# source_eagle.net
KiCad netlist of a schematic drawn in EAGLE
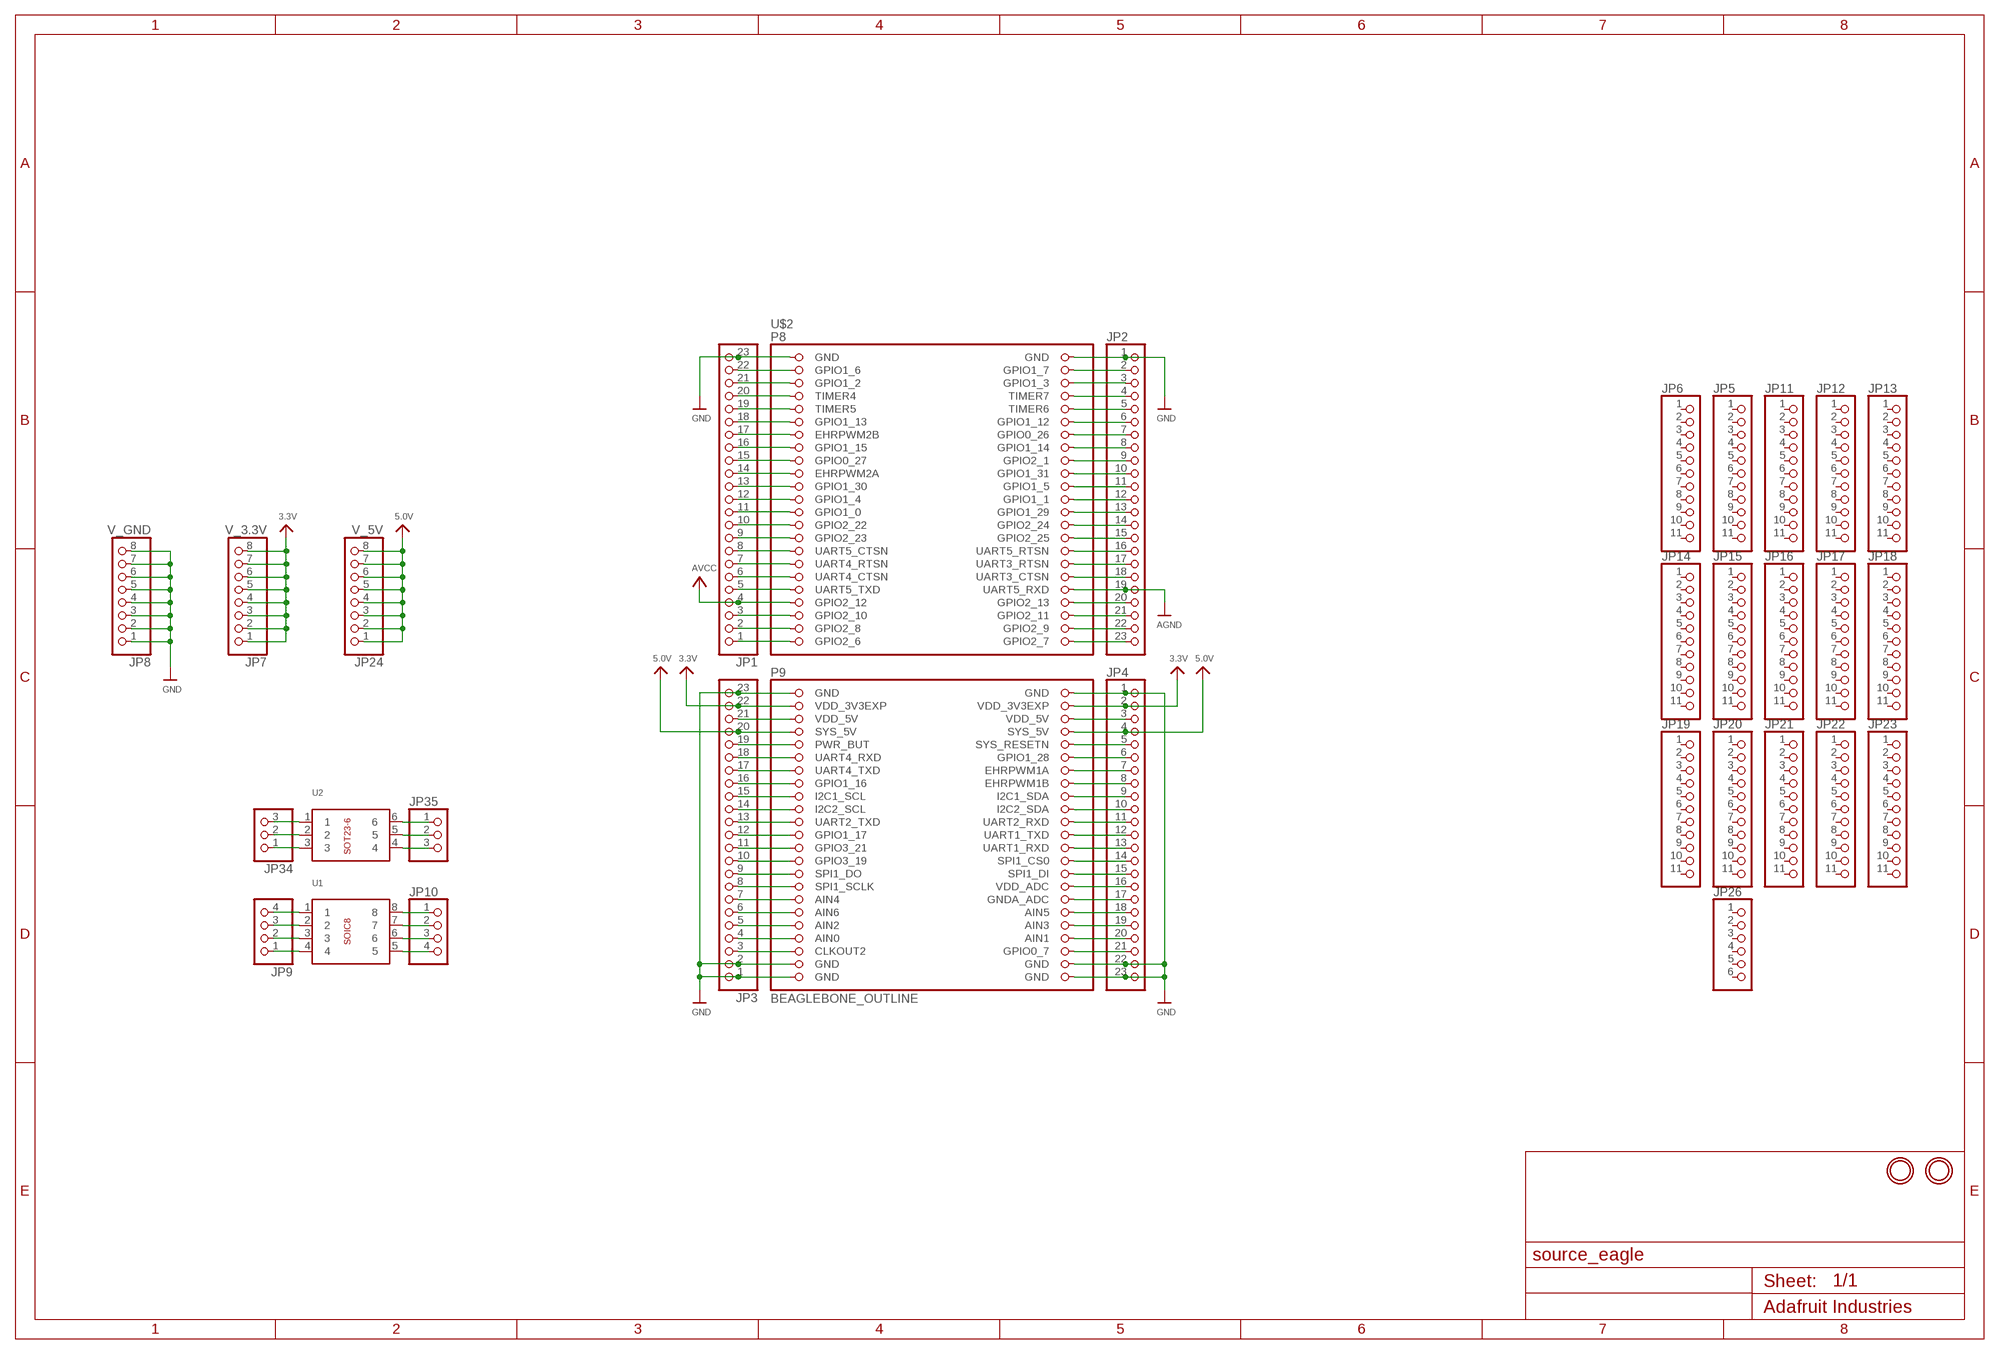
[diagram p0: schematic, sheet 1]

(export (version "E")
  (design (tool "Eeschema 10.0.6"))
  (components
    (comp (ref "JP1")
      (value "HEADER-1X23")
      (footprint "eagle-import:1X23_ROUND_70MIL")
      (libsource (lib "eagle-import") (part "HEADER-1X23"))
    )
    (comp (ref "JP2")
      (value "HEADER-1X23")
      (footprint "eagle-import:1X23_ROUND_70MIL")
      (libsource (lib "eagle-import") (part "HEADER-1X23"))
    )
    (comp (ref "JP3")
      (value "HEADER-1X23")
      (footprint "eagle-import:1X23_ROUND_70MIL")
      (libsource (lib "eagle-import") (part "HEADER-1X23"))
    )
    (comp (ref "JP4")
      (value "HEADER-1X23")
      (footprint "eagle-import:1X23_ROUND_70MIL")
      (libsource (lib "eagle-import") (part "HEADER-1X23"))
    )
    (comp (ref "JP5")
      (value "HEADER-1X1176MIL")
      (footprint "eagle-import:1X11_ROUND_76")
      (libsource (lib "eagle-import") (part "HEADER-1X1176MIL"))
    )
    (comp (ref "JP6")
      (value "HEADER-1X1176MIL")
      (footprint "eagle-import:1X11_ROUND_76")
      (libsource (lib "eagle-import") (part "HEADER-1X1176MIL"))
    )
    (comp (ref "JP7")
      (value "V_3.3V")
      (footprint "eagle-import:1X08_ROUND_70")
      (libsource (lib "eagle-import") (part "HEADER-1X870MIL"))
    )
    (comp (ref "JP8")
      (value "V_GND")
      (footprint "eagle-import:1X08_ROUND_70")
      (libsource (lib "eagle-import") (part "HEADER-1X870MIL"))
    )
    (comp (ref "JP9")
      (value "HEADER-1X476MIL")
      (footprint "eagle-import:1X04_ROUND_76")
      (libsource (lib "eagle-import") (part "HEADER-1X476MIL"))
    )
    (comp (ref "JP10")
      (value "HEADER-1X476MIL")
      (footprint "eagle-import:1X04_ROUND_76")
      (libsource (lib "eagle-import") (part "HEADER-1X476MIL"))
    )
    (comp (ref "JP11")
      (value "HEADER-1X1176MIL")
      (footprint "eagle-import:1X11_ROUND_76")
      (libsource (lib "eagle-import") (part "HEADER-1X1176MIL"))
    )
    (comp (ref "JP12")
      (value "HEADER-1X1176MIL")
      (footprint "eagle-import:1X11_ROUND_76")
      (libsource (lib "eagle-import") (part "HEADER-1X1176MIL"))
    )
    (comp (ref "JP13")
      (value "HEADER-1X1176MIL")
      (footprint "eagle-import:1X11_ROUND_76")
      (libsource (lib "eagle-import") (part "HEADER-1X1176MIL"))
    )
    (comp (ref "JP14")
      (value "HEADER-1X1176MIL")
      (footprint "eagle-import:1X11_ROUND_76")
      (libsource (lib "eagle-import") (part "HEADER-1X1176MIL"))
    )
    (comp (ref "JP15")
      (value "HEADER-1X1176MIL")
      (footprint "eagle-import:1X11_ROUND_76")
      (libsource (lib "eagle-import") (part "HEADER-1X1176MIL"))
    )
    (comp (ref "JP16")
      (value "HEADER-1X1176MIL")
      (footprint "eagle-import:1X11_ROUND_76")
      (libsource (lib "eagle-import") (part "HEADER-1X1176MIL"))
    )
    (comp (ref "JP17")
      (value "HEADER-1X1176MIL")
      (footprint "eagle-import:1X11_ROUND_76")
      (libsource (lib "eagle-import") (part "HEADER-1X1176MIL"))
    )
    (comp (ref "JP18")
      (value "HEADER-1X1176MIL")
      (footprint "eagle-import:1X11_ROUND_76")
      (libsource (lib "eagle-import") (part "HEADER-1X1176MIL"))
    )
    (comp (ref "JP19")
      (value "HEADER-1X1176MIL")
      (footprint "eagle-import:1X11_ROUND_76")
      (libsource (lib "eagle-import") (part "HEADER-1X1176MIL"))
    )
    (comp (ref "JP20")
      (value "HEADER-1X1176MIL")
      (footprint "eagle-import:1X11_ROUND_76")
      (libsource (lib "eagle-import") (part "HEADER-1X1176MIL"))
    )
    (comp (ref "JP21")
      (value "HEADER-1X1176MIL")
      (footprint "eagle-import:1X11_ROUND_76")
      (libsource (lib "eagle-import") (part "HEADER-1X1176MIL"))
    )
    (comp (ref "JP22")
      (value "HEADER-1X1176MIL")
      (footprint "eagle-import:1X11_ROUND_76")
      (libsource (lib "eagle-import") (part "HEADER-1X1176MIL"))
    )
    (comp (ref "JP23")
      (value "HEADER-1X1176MIL")
      (footprint "eagle-import:1X11_ROUND_76")
      (libsource (lib "eagle-import") (part "HEADER-1X1176MIL"))
    )
    (comp (ref "JP24")
      (value "V_5V")
      (footprint "eagle-import:1X08_ROUND_70")
      (libsource (lib "eagle-import") (part "HEADER-1X870MIL"))
    )
    (comp (ref "JP26")
      (value "HEADER-1X676MIL")
      (footprint "eagle-import:1X06_ROUND_76")
      (libsource (lib "eagle-import") (part "HEADER-1X676MIL"))
    )
    (comp (ref "JP34")
      (value "HEADER-1X376MIL")
      (footprint "eagle-import:1X03_ROUND_76")
      (libsource (lib "eagle-import") (part "HEADER-1X376MIL"))
    )
    (comp (ref "JP35")
      (value "HEADER-1X376MIL")
      (footprint "eagle-import:1X03_ROUND_76")
      (libsource (lib "eagle-import") (part "HEADER-1X376MIL"))
    )
    (comp (ref "U$2")
      (value "BEAGLEBONE_OUTLINE")
      (footprint "eagle-import:BEAGLEBONE_SHIELD")
      (libsource (lib "eagle-import") (part "BEAGLEBONE_OUTLINE"))
    )
    (comp (ref "U$22")
      (value "MOUNTINGHOLE3.0THIN")
      (footprint "eagle-import:MOUNTINGHOLE_3.0_PLATEDTHIN")
      (libsource (lib "eagle-import") (part "MOUNTINGHOLE3.0THIN"))
    )
    (comp (ref "U$23")
      (value "MOUNTINGHOLE3.0THIN")
      (footprint "eagle-import:MOUNTINGHOLE_3.0_PLATEDTHIN")
      (libsource (lib "eagle-import") (part "MOUNTINGHOLE3.0THIN"))
    )
    (comp (ref "U1")
      (value "BREAKOUT_SOIC8")
      (footprint "eagle-import:BREAKOUT_SOIC8")
      (libsource (lib "eagle-import") (part "BREAKOUT_SOIC8"))
    )
    (comp (ref "U2")
      (value "BREAKOUT_SOT23-6")
      (footprint "eagle-import:BREAKOUT_SOT23-6")
      (libsource (lib "eagle-import") (part "BREAKOUT_SOT23-6"))
    )
  )
  (nets
    (net (code "1") (name "3.3V") (class "Default")
      (node (ref "JP3") (pin "22") (pinfunction "22_22") (pintype "passive"))
      (node (ref "JP4") (pin "2") (pinfunction "2_2") (pintype "passive"))
      (node (ref "JP7") (pin "1") (pinfunction "1_1") (pintype "passive"))
      (node (ref "JP7") (pin "2") (pinfunction "2_2") (pintype "passive"))
      (node (ref "JP7") (pin "3") (pinfunction "3_3") (pintype "passive"))
      (node (ref "JP7") (pin "4") (pinfunction "4_4") (pintype "passive"))
      (node (ref "JP7") (pin "5") (pinfunction "5_5") (pintype "passive"))
      (node (ref "JP7") (pin "6") (pinfunction "6_6") (pintype "passive"))
      (node (ref "JP7") (pin "7") (pinfunction "7_7") (pintype "passive"))
      (node (ref "JP7") (pin "8") (pinfunction "8_8") (pintype "passive"))
      (node (ref "U$2") (pin "49") (pinfunction "VDD_3V3EXP_49") (pintype "power_in"))
      (node (ref "U$2") (pin "50") (pinfunction "VDD_3V3EXP_50") (pintype "power_in"))
    )
    (net (code "2") (name "5.0V") (class "Default")
      (node (ref "JP24") (pin "1") (pinfunction "1_1") (pintype "passive"))
      (node (ref "JP24") (pin "2") (pinfunction "2_2") (pintype "passive"))
      (node (ref "JP24") (pin "3") (pinfunction "3_3") (pintype "passive"))
      (node (ref "JP24") (pin "4") (pinfunction "4_4") (pintype "passive"))
      (node (ref "JP24") (pin "5") (pinfunction "5_5") (pintype "passive"))
      (node (ref "JP24") (pin "6") (pinfunction "6_6") (pintype "passive"))
      (node (ref "JP24") (pin "7") (pinfunction "7_7") (pintype "passive"))
      (node (ref "JP24") (pin "8") (pinfunction "8_8") (pintype "passive"))
      (node (ref "JP3") (pin "20") (pinfunction "20_20") (pintype "passive"))
      (node (ref "JP4") (pin "4") (pinfunction "4_4") (pintype "passive"))
      (node (ref "U$2") (pin "53") (pinfunction "SYS_5V_53") (pintype "passive"))
      (node (ref "U$2") (pin "54") (pinfunction "SYS_5V_54") (pintype "passive"))
    )
    (net (code "3") (name "AGND") (class "Default")
      (node (ref "JP2") (pin "19") (pinfunction "19_19") (pintype "passive"))
      (node (ref "U$2") (pin "38") (pinfunction "UART5_RXD_38") (pintype "passive"))
    )
    (net (code "4") (name "AVCC") (class "Default")
      (node (ref "JP1") (pin "4") (pinfunction "4_4") (pintype "passive"))
      (node (ref "U$2") (pin "39") (pinfunction "GPIO2_12_39") (pintype "passive"))
    )
    (net (code "5") (name "GND") (class "Default")
      (node (ref "JP1") (pin "23") (pinfunction "23_23") (pintype "passive"))
      (node (ref "JP2") (pin "1") (pinfunction "1_1") (pintype "passive"))
      (node (ref "JP3") (pin "1") (pinfunction "1_1") (pintype "passive"))
      (node (ref "JP3") (pin "2") (pinfunction "2_2") (pintype "passive"))
      (node (ref "JP3") (pin "23") (pinfunction "23_23") (pintype "passive"))
      (node (ref "JP4") (pin "1") (pinfunction "1_1") (pintype "passive"))
      (node (ref "JP4") (pin "22") (pinfunction "22_22") (pintype "passive"))
      (node (ref "JP4") (pin "23") (pinfunction "23_23") (pintype "passive"))
      (node (ref "JP8") (pin "1") (pinfunction "1_1") (pintype "passive"))
      (node (ref "JP8") (pin "2") (pinfunction "2_2") (pintype "passive"))
      (node (ref "JP8") (pin "3") (pinfunction "3_3") (pintype "passive"))
      (node (ref "JP8") (pin "4") (pinfunction "4_4") (pintype "passive"))
      (node (ref "JP8") (pin "5") (pinfunction "5_5") (pintype "passive"))
      (node (ref "JP8") (pin "6") (pinfunction "6_6") (pintype "passive"))
      (node (ref "JP8") (pin "7") (pinfunction "7_7") (pintype "passive"))
      (node (ref "JP8") (pin "8") (pinfunction "8_8") (pintype "passive"))
      (node (ref "U$2") (pin "1") (pinfunction "GND_1") (pintype "power_in"))
      (node (ref "U$2") (pin "2") (pinfunction "GND_2") (pintype "power_in"))
      (node (ref "U$2") (pin "47") (pinfunction "GND_47") (pintype "power_in"))
      (node (ref "U$2") (pin "48") (pinfunction "GND_48") (pintype "power_in"))
      (node (ref "U$2") (pin "89") (pinfunction "GND_89") (pintype "input"))
      (node (ref "U$2") (pin "90") (pinfunction "GND_90") (pintype "input"))
      (node (ref "U$2") (pin "91") (pinfunction "GND_91") (pintype "input"))
      (node (ref "U$2") (pin "92") (pinfunction "GND_92") (pintype "input"))
    )
    (net (code "6") (name "Net-(JP3-Pad21)") (class "Default")
      (node (ref "JP3") (pin "21") (pinfunction "21_21") (pintype "passive"))
      (node (ref "U$2") (pin "51") (pinfunction "VDD_5V_51") (pintype "power_in"))
    )
    (net (code "7") (name "Net-(JP4-Pad3)") (class "Default")
      (node (ref "JP4") (pin "3") (pinfunction "3_3") (pintype "passive"))
      (node (ref "U$2") (pin "52") (pinfunction "VDD_5V_52") (pintype "power_in"))
    )
    (net (code "8") (name "Net-(JP9-Pad1)") (class "Default")
      (node (ref "JP9") (pin "1") (pinfunction "1_1") (pintype "passive"))
      (node (ref "U1") (pin "4") (pinfunction "4_4") (pintype "bidirectional"))
    )
    (net (code "9") (name "Net-(JP9-Pad2)") (class "Default")
      (node (ref "JP9") (pin "2") (pinfunction "2_2") (pintype "passive"))
      (node (ref "U1") (pin "3") (pinfunction "3_3") (pintype "bidirectional"))
    )
    (net (code "10") (name "Net-(JP9-Pad3)") (class "Default")
      (node (ref "JP9") (pin "3") (pinfunction "3_3") (pintype "passive"))
      (node (ref "U1") (pin "2") (pinfunction "2_2") (pintype "bidirectional"))
    )
    (net (code "11") (name "Net-(JP9-Pad4)") (class "Default")
      (node (ref "JP9") (pin "4") (pinfunction "4_4") (pintype "passive"))
      (node (ref "U1") (pin "1") (pinfunction "1_1") (pintype "bidirectional"))
    )
    (net (code "12") (name "Net-(JP10-Pad1)") (class "Default")
      (node (ref "JP10") (pin "1") (pinfunction "1_1") (pintype "passive"))
      (node (ref "U1") (pin "8") (pinfunction "8_8") (pintype "bidirectional"))
    )
    (net (code "13") (name "Net-(JP10-Pad2)") (class "Default")
      (node (ref "JP10") (pin "2") (pinfunction "2_2") (pintype "passive"))
      (node (ref "U1") (pin "7") (pinfunction "7_7") (pintype "bidirectional"))
    )
    (net (code "14") (name "Net-(JP10-Pad3)") (class "Default")
      (node (ref "JP10") (pin "3") (pinfunction "3_3") (pintype "passive"))
      (node (ref "U1") (pin "6") (pinfunction "6_6") (pintype "bidirectional"))
    )
    (net (code "15") (name "Net-(JP10-Pad4)") (class "Default")
      (node (ref "JP10") (pin "4") (pinfunction "4_4") (pintype "passive"))
      (node (ref "U1") (pin "5") (pinfunction "5_5") (pintype "bidirectional"))
    )
    (net (code "16") (name "Net-(JP34-Pad1)") (class "Default")
      (node (ref "JP34") (pin "1") (pinfunction "1_1") (pintype "passive"))
      (node (ref "U2") (pin "3") (pinfunction "3_3") (pintype "bidirectional"))
    )
    (net (code "17") (name "Net-(JP34-Pad2)") (class "Default")
      (node (ref "JP34") (pin "2") (pinfunction "2_2") (pintype "passive"))
      (node (ref "U2") (pin "2") (pinfunction "2_2") (pintype "bidirectional"))
    )
    (net (code "18") (name "Net-(JP34-Pad3)") (class "Default")
      (node (ref "JP34") (pin "3") (pinfunction "3_3") (pintype "passive"))
      (node (ref "U2") (pin "1") (pinfunction "1_1") (pintype "bidirectional"))
    )
    (net (code "19") (name "Net-(JP35-Pad1)") (class "Default")
      (node (ref "JP35") (pin "1") (pinfunction "1_1") (pintype "passive"))
      (node (ref "U2") (pin "6") (pinfunction "6_6") (pintype "bidirectional"))
    )
    (net (code "20") (name "Net-(JP35-Pad2)") (class "Default")
      (node (ref "JP35") (pin "2") (pinfunction "2_2") (pintype "passive"))
      (node (ref "U2") (pin "5") (pinfunction "5_5") (pintype "bidirectional"))
    )
    (net (code "21") (name "Net-(JP35-Pad3)") (class "Default")
      (node (ref "JP35") (pin "3") (pinfunction "3_3") (pintype "passive"))
      (node (ref "U2") (pin "4") (pinfunction "4_4") (pintype "bidirectional"))
    )
    (net (code "22") (name "Net-(U$2-AIN0)") (class "Default")
      (node (ref "JP3") (pin "4") (pinfunction "4_4") (pintype "passive"))
      (node (ref "U$2") (pin "85") (pinfunction "AIN0_85") (pintype "power_in"))
    )
    (net (code "23") (name "Net-(U$2-AIN1)") (class "Default")
      (node (ref "JP4") (pin "20") (pinfunction "20_20") (pintype "passive"))
      (node (ref "U$2") (pin "86") (pinfunction "AIN1_86") (pintype "input"))
    )
    (net (code "24") (name "Net-(U$2-AIN2)") (class "Default")
      (node (ref "JP3") (pin "5") (pinfunction "5_5") (pintype "passive"))
      (node (ref "U$2") (pin "83") (pinfunction "AIN2_83") (pintype "passive"))
    )
    (net (code "25") (name "Net-(U$2-AIN3)") (class "Default")
      (node (ref "JP4") (pin "19") (pinfunction "19_19") (pintype "passive"))
      (node (ref "U$2") (pin "84") (pinfunction "AIN3_84") (pintype "power_in"))
    )
    (net (code "26") (name "Net-(U$2-AIN4)") (class "Default")
      (node (ref "JP3") (pin "7") (pinfunction "7_7") (pintype "passive"))
      (node (ref "U$2") (pin "79") (pinfunction "AIN4_79") (pintype "passive"))
    )
    (net (code "27") (name "Net-(U$2-AIN5)") (class "Default")
      (node (ref "JP4") (pin "18") (pinfunction "18_18") (pintype "passive"))
      (node (ref "U$2") (pin "82") (pinfunction "AIN5_82") (pintype "passive"))
    )
    (net (code "28") (name "Net-(U$2-AIN6)") (class "Default")
      (node (ref "JP3") (pin "6") (pinfunction "6_6") (pintype "passive"))
      (node (ref "U$2") (pin "81") (pinfunction "AIN6_81") (pintype "passive"))
    )
    (net (code "29") (name "Net-(U$2-CLKOUT2)") (class "Default")
      (node (ref "JP3") (pin "3") (pinfunction "3_3") (pintype "passive"))
      (node (ref "U$2") (pin "87") (pinfunction "CLKOUT2_87") (pintype "input"))
    )
    (net (code "30") (name "Net-(U$2-EHRPWM1A)") (class "Default")
      (node (ref "JP4") (pin "7") (pinfunction "7_7") (pintype "passive"))
      (node (ref "U$2") (pin "60") (pinfunction "EHRPWM1A_60") (pintype "passive"))
    )
    (net (code "31") (name "Net-(U$2-EHRPWM1B)") (class "Default")
      (node (ref "JP4") (pin "8") (pinfunction "8_8") (pintype "passive"))
      (node (ref "U$2") (pin "62") (pinfunction "EHRPWM1B_62") (pintype "passive"))
    )
    (net (code "32") (name "Net-(U$2-EHRPWM2A)") (class "Default")
      (node (ref "JP1") (pin "14") (pinfunction "14_14") (pintype "passive"))
      (node (ref "U$2") (pin "19") (pinfunction "EHRPWM2A_19") (pintype "passive"))
    )
    (net (code "33") (name "Net-(U$2-EHRPWM2B)") (class "Default")
      (node (ref "JP1") (pin "17") (pinfunction "17_17") (pintype "passive"))
      (node (ref "U$2") (pin "13") (pinfunction "EHRPWM2B_13") (pintype "passive"))
    )
    (net (code "34") (name "Net-(U$2-GNDA_ADC)") (class "Default")
      (node (ref "JP4") (pin "17") (pinfunction "17_17") (pintype "passive"))
      (node (ref "U$2") (pin "80") (pinfunction "GNDA_ADC_80") (pintype "passive"))
    )
    (net (code "35") (name "Net-(U$2-GPIO0_7)") (class "Default")
      (node (ref "JP4") (pin "21") (pinfunction "21_21") (pintype "passive"))
      (node (ref "U$2") (pin "88") (pinfunction "GPIO0_7_88") (pintype "input"))
    )
    (net (code "36") (name "Net-(U$2-GPIO0_26)") (class "Default")
      (node (ref "JP2") (pin "7") (pinfunction "7_7") (pintype "passive"))
      (node (ref "U$2") (pin "14") (pinfunction "GPIO0_26_14") (pintype "passive"))
    )
    (net (code "37") (name "Net-(U$2-GPIO0_27)") (class "Default")
      (node (ref "JP1") (pin "15") (pinfunction "15_15") (pintype "passive"))
      (node (ref "U$2") (pin "17") (pinfunction "GPIO0_27_17") (pintype "passive"))
    )
    (net (code "38") (name "Net-(U$2-GPIO1_0)") (class "Default")
      (node (ref "JP1") (pin "11") (pinfunction "11_11") (pintype "passive"))
      (node (ref "U$2") (pin "25") (pinfunction "GPIO1_0_25") (pintype "passive"))
    )
    (net (code "39") (name "Net-(U$2-GPIO1_1)") (class "Default")
      (node (ref "JP2") (pin "12") (pinfunction "12_12") (pintype "passive"))
      (node (ref "U$2") (pin "24") (pinfunction "GPIO1_1_24") (pintype "passive"))
    )
    (net (code "40") (name "Net-(U$2-GPIO1_2)") (class "Default")
      (node (ref "JP1") (pin "21") (pinfunction "21_21") (pintype "passive"))
      (node (ref "U$2") (pin "5") (pinfunction "GPIO1_2_5") (pintype "passive"))
    )
    (net (code "41") (name "Net-(U$2-GPIO1_3)") (class "Default")
      (node (ref "JP2") (pin "3") (pinfunction "3_3") (pintype "passive"))
      (node (ref "U$2") (pin "6") (pinfunction "GPIO1_3_6") (pintype "passive"))
    )
    (net (code "42") (name "Net-(U$2-GPIO1_4)") (class "Default")
      (node (ref "JP1") (pin "12") (pinfunction "12_12") (pintype "passive"))
      (node (ref "U$2") (pin "23") (pinfunction "GPIO1_4_23") (pintype "passive"))
    )
    (net (code "43") (name "Net-(U$2-GPIO1_5)") (class "Default")
      (node (ref "JP2") (pin "11") (pinfunction "11_11") (pintype "passive"))
      (node (ref "U$2") (pin "22") (pinfunction "GPIO1_5_22") (pintype "passive"))
    )
    (net (code "44") (name "Net-(U$2-GPIO1_6)") (class "Default")
      (node (ref "JP1") (pin "22") (pinfunction "22_22") (pintype "passive"))
      (node (ref "U$2") (pin "3") (pinfunction "GPIO1_6_3") (pintype "power_in"))
    )
    (net (code "45") (name "Net-(U$2-GPIO1_7)") (class "Default")
      (node (ref "JP2") (pin "2") (pinfunction "2_2") (pintype "passive"))
      (node (ref "U$2") (pin "4") (pinfunction "GPIO1_7_4") (pintype "power_in"))
    )
    (net (code "46") (name "Net-(U$2-GPIO1_12)") (class "Default")
      (node (ref "JP2") (pin "6") (pinfunction "6_6") (pintype "passive"))
      (node (ref "U$2") (pin "12") (pinfunction "GPIO1_12_12") (pintype "passive"))
    )
    (net (code "47") (name "Net-(U$2-GPIO1_13)") (class "Default")
      (node (ref "JP1") (pin "18") (pinfunction "18_18") (pintype "passive"))
      (node (ref "U$2") (pin "11") (pinfunction "GPIO1_13_11") (pintype "passive"))
    )
    (net (code "48") (name "Net-(U$2-GPIO1_14)") (class "Default")
      (node (ref "JP2") (pin "8") (pinfunction "8_8") (pintype "passive"))
      (node (ref "U$2") (pin "16") (pinfunction "GPIO1_14_16") (pintype "passive"))
    )
    (net (code "49") (name "Net-(U$2-GPIO1_15)") (class "Default")
      (node (ref "JP1") (pin "16") (pinfunction "16_16") (pintype "passive"))
      (node (ref "U$2") (pin "15") (pinfunction "GPIO1_15_15") (pintype "passive"))
    )
    (net (code "50") (name "Net-(U$2-GPIO1_16)") (class "Default")
      (node (ref "JP3") (pin "16") (pinfunction "16_16") (pintype "passive"))
      (node (ref "U$2") (pin "61") (pinfunction "GPIO1_16_61") (pintype "passive"))
    )
    (net (code "51") (name "Net-(U$2-GPIO1_17)") (class "Default")
      (node (ref "JP3") (pin "12") (pinfunction "12_12") (pintype "passive"))
      (node (ref "U$2") (pin "69") (pinfunction "GPIO1_17_69") (pintype "passive"))
    )
    (net (code "52") (name "Net-(U$2-GPIO1_28)") (class "Default")
      (node (ref "JP4") (pin "6") (pinfunction "6_6") (pintype "passive"))
      (node (ref "U$2") (pin "58") (pinfunction "GPIO1_28_58") (pintype "passive"))
    )
    (net (code "53") (name "Net-(U$2-GPIO1_29)") (class "Default")
      (node (ref "JP2") (pin "13") (pinfunction "13_13") (pintype "passive"))
      (node (ref "U$2") (pin "26") (pinfunction "GPIO1_29_26") (pintype "passive"))
    )
    (net (code "54") (name "Net-(U$2-GPIO1_30)") (class "Default")
      (node (ref "JP1") (pin "13") (pinfunction "13_13") (pintype "passive"))
      (node (ref "U$2") (pin "21") (pinfunction "GPIO1_30_21") (pintype "passive"))
    )
    (net (code "55") (name "Net-(U$2-GPIO1_31)") (class "Default")
      (node (ref "JP2") (pin "10") (pinfunction "10_10") (pintype "passive"))
      (node (ref "U$2") (pin "20") (pinfunction "GPIO1_31_20") (pintype "passive"))
    )
    (net (code "56") (name "Net-(U$2-GPIO2_1)") (class "Default")
      (node (ref "JP2") (pin "9") (pinfunction "9_9") (pintype "passive"))
      (node (ref "U$2") (pin "18") (pinfunction "GPIO2_1_18") (pintype "passive"))
    )
    (net (code "57") (name "Net-(U$2-GPIO2_6)") (class "Default")
      (node (ref "JP1") (pin "1") (pinfunction "1_1") (pintype "passive"))
      (node (ref "U$2") (pin "45") (pinfunction "GPIO2_6_45") (pintype "power_in"))
    )
    (net (code "58") (name "Net-(U$2-GPIO2_7)") (class "Default")
      (node (ref "JP2") (pin "23") (pinfunction "23_23") (pintype "passive"))
      (node (ref "U$2") (pin "46") (pinfunction "GPIO2_7_46") (pintype "power_in"))
    )
    (net (code "59") (name "Net-(U$2-GPIO2_8)") (class "Default")
      (node (ref "JP1") (pin "2") (pinfunction "2_2") (pintype "passive"))
      (node (ref "U$2") (pin "43") (pinfunction "GPIO2_8_43") (pintype "power_in"))
    )
    (net (code "60") (name "Net-(U$2-GPIO2_9)") (class "Default")
      (node (ref "JP2") (pin "22") (pinfunction "22_22") (pintype "passive"))
      (node (ref "U$2") (pin "44") (pinfunction "GPIO2_9_44") (pintype "power_in"))
    )
    (net (code "61") (name "Net-(U$2-GPIO2_10)") (class "Default")
      (node (ref "JP1") (pin "3") (pinfunction "3_3") (pintype "passive"))
      (node (ref "U$2") (pin "41") (pinfunction "GPIO2_10_41") (pintype "passive"))
    )
    (net (code "62") (name "Net-(U$2-GPIO2_11)") (class "Default")
      (node (ref "JP2") (pin "21") (pinfunction "21_21") (pintype "passive"))
      (node (ref "U$2") (pin "42") (pinfunction "GPIO2_11_42") (pintype "power_in"))
    )
    (net (code "63") (name "Net-(U$2-GPIO2_13)") (class "Default")
      (node (ref "JP2") (pin "20") (pinfunction "20_20") (pintype "passive"))
      (node (ref "U$2") (pin "40") (pinfunction "GPIO2_13_40") (pintype "passive"))
    )
    (net (code "64") (name "Net-(U$2-GPIO2_22)") (class "Default")
      (node (ref "JP1") (pin "10") (pinfunction "10_10") (pintype "passive"))
      (node (ref "U$2") (pin "27") (pinfunction "GPIO2_22_27") (pintype "passive"))
    )
    (net (code "65") (name "Net-(U$2-GPIO2_23)") (class "Default")
      (node (ref "JP1") (pin "9") (pinfunction "9_9") (pintype "passive"))
      (node (ref "U$2") (pin "29") (pinfunction "GPIO2_23_29") (pintype "passive"))
    )
    (net (code "66") (name "Net-(U$2-GPIO2_24)") (class "Default")
      (node (ref "JP2") (pin "14") (pinfunction "14_14") (pintype "passive"))
      (node (ref "U$2") (pin "28") (pinfunction "GPIO2_24_28") (pintype "passive"))
    )
    (net (code "67") (name "Net-(U$2-GPIO2_25)") (class "Default")
      (node (ref "JP2") (pin "15") (pinfunction "15_15") (pintype "passive"))
      (node (ref "U$2") (pin "30") (pinfunction "GPIO2_25_30") (pintype "passive"))
    )
    (net (code "68") (name "Net-(U$2-GPIO3_19)") (class "Default")
      (node (ref "JP3") (pin "10") (pinfunction "10_10") (pintype "passive"))
      (node (ref "U$2") (pin "73") (pinfunction "GPIO3_19_73") (pintype "passive"))
    )
    (net (code "69") (name "Net-(U$2-GPIO3_21)") (class "Default")
      (node (ref "JP3") (pin "11") (pinfunction "11_11") (pintype "passive"))
      (node (ref "U$2") (pin "71") (pinfunction "GPIO3_21_71") (pintype "passive"))
    )
    (net (code "70") (name "Net-(U$2-I2C1_SCL)") (class "Default")
      (node (ref "JP3") (pin "15") (pinfunction "15_15") (pintype "passive"))
      (node (ref "U$2") (pin "63") (pinfunction "I2C1_SCL_63") (pintype "passive"))
    )
    (net (code "71") (name "Net-(U$2-I2C1_SDA)") (class "Default")
      (node (ref "JP4") (pin "9") (pinfunction "9_9") (pintype "passive"))
      (node (ref "U$2") (pin "64") (pinfunction "I2C1_SDA_64") (pintype "passive"))
    )
    (net (code "72") (name "Net-(U$2-I2C2_SCL)") (class "Default")
      (node (ref "JP3") (pin "14") (pinfunction "14_14") (pintype "passive"))
      (node (ref "U$2") (pin "65") (pinfunction "I2C2_SCL_65") (pintype "passive"))
    )
    (net (code "73") (name "Net-(U$2-I2C2_SDA)") (class "Default")
      (node (ref "JP4") (pin "10") (pinfunction "10_10") (pintype "passive"))
      (node (ref "U$2") (pin "66") (pinfunction "I2C2_SDA_66") (pintype "passive"))
    )
    (net (code "74") (name "Net-(U$2-PWR_BUT)") (class "Default")
      (node (ref "JP3") (pin "19") (pinfunction "19_19") (pintype "passive"))
      (node (ref "U$2") (pin "55") (pinfunction "PWR_BUT_55") (pintype "passive"))
    )
    (net (code "75") (name "Net-(U$2-SPI1_CS0)") (class "Default")
      (node (ref "JP4") (pin "14") (pinfunction "14_14") (pintype "passive"))
      (node (ref "U$2") (pin "74") (pinfunction "SPI1_CS0_74") (pintype "passive"))
    )
    (net (code "76") (name "Net-(U$2-SPI1_DI)") (class "Default")
      (node (ref "JP4") (pin "15") (pinfunction "15_15") (pintype "passive"))
      (node (ref "U$2") (pin "76") (pinfunction "SPI1_DI_76") (pintype "passive"))
    )
    (net (code "77") (name "Net-(U$2-SPI1_DO)") (class "Default")
      (node (ref "JP3") (pin "9") (pinfunction "9_9") (pintype "passive"))
      (node (ref "U$2") (pin "75") (pinfunction "SPI1_DO_75") (pintype "passive"))
    )
    (net (code "78") (name "Net-(U$2-SPI1_SCLK)") (class "Default")
      (node (ref "JP3") (pin "8") (pinfunction "8_8") (pintype "passive"))
      (node (ref "U$2") (pin "77") (pinfunction "SPI1_SCLK_77") (pintype "passive"))
    )
    (net (code "79") (name "Net-(U$2-SYS_RESETN)") (class "Default")
      (node (ref "JP4") (pin "5") (pinfunction "5_5") (pintype "passive"))
      (node (ref "U$2") (pin "56") (pinfunction "SYS_RESETN_56") (pintype "passive"))
    )
    (net (code "80") (name "Net-(U$2-TIMER4)") (class "Default")
      (node (ref "JP1") (pin "20") (pinfunction "20_20") (pintype "passive"))
      (node (ref "U$2") (pin "7") (pinfunction "TIMER4_7") (pintype "passive"))
    )
    (net (code "81") (name "Net-(U$2-TIMER5)") (class "Default")
      (node (ref "JP1") (pin "19") (pinfunction "19_19") (pintype "passive"))
      (node (ref "U$2") (pin "9") (pinfunction "TIMER5_9") (pintype "passive"))
    )
    (net (code "82") (name "Net-(U$2-TIMER6)") (class "Default")
      (node (ref "JP2") (pin "5") (pinfunction "5_5") (pintype "passive"))
      (node (ref "U$2") (pin "10") (pinfunction "TIMER6_10") (pintype "passive"))
    )
    (net (code "83") (name "Net-(U$2-TIMER7)") (class "Default")
      (node (ref "JP2") (pin "4") (pinfunction "4_4") (pintype "passive"))
      (node (ref "U$2") (pin "8") (pinfunction "TIMER7_8") (pintype "passive"))
    )
    (net (code "84") (name "Net-(U$2-UART1_RXD)") (class "Default")
      (node (ref "JP4") (pin "13") (pinfunction "13_13") (pintype "passive"))
      (node (ref "U$2") (pin "72") (pinfunction "UART1_RXD_72") (pintype "passive"))
    )
    (net (code "85") (name "Net-(U$2-UART1_TXD)") (class "Default")
      (node (ref "JP4") (pin "12") (pinfunction "12_12") (pintype "passive"))
      (node (ref "U$2") (pin "70") (pinfunction "UART1_TXD_70") (pintype "passive"))
    )
    (net (code "86") (name "Net-(U$2-UART2_RXD)") (class "Default")
      (node (ref "JP4") (pin "11") (pinfunction "11_11") (pintype "passive"))
      (node (ref "U$2") (pin "68") (pinfunction "UART2_RXD_68") (pintype "passive"))
    )
    (net (code "87") (name "Net-(U$2-UART2_TXD)") (class "Default")
      (node (ref "JP3") (pin "13") (pinfunction "13_13") (pintype "passive"))
      (node (ref "U$2") (pin "67") (pinfunction "UART2_TXD_67") (pintype "passive"))
    )
    (net (code "88") (name "Net-(U$2-UART3_CTSN)") (class "Default")
      (node (ref "JP2") (pin "18") (pinfunction "18_18") (pintype "passive"))
      (node (ref "U$2") (pin "36") (pinfunction "UART3_CTSN_36") (pintype "passive"))
    )
    (net (code "89") (name "Net-(U$2-UART3_RTSN)") (class "Default")
      (node (ref "JP2") (pin "17") (pinfunction "17_17") (pintype "passive"))
      (node (ref "U$2") (pin "34") (pinfunction "UART3_RTSN_34") (pintype "passive"))
    )
    (net (code "90") (name "Net-(U$2-UART4_CTSN)") (class "Default")
      (node (ref "JP1") (pin "6") (pinfunction "6_6") (pintype "passive"))
      (node (ref "U$2") (pin "35") (pinfunction "UART4_CTSN_35") (pintype "passive"))
    )
    (net (code "91") (name "Net-(U$2-UART4_RTSN)") (class "Default")
      (node (ref "JP1") (pin "7") (pinfunction "7_7") (pintype "passive"))
      (node (ref "U$2") (pin "33") (pinfunction "UART4_RTSN_33") (pintype "passive"))
    )
    (net (code "92") (name "Net-(U$2-UART4_RXD)") (class "Default")
      (node (ref "JP3") (pin "18") (pinfunction "18_18") (pintype "passive"))
      (node (ref "U$2") (pin "57") (pinfunction "UART4_RXD_57") (pintype "passive"))
    )
    (net (code "93") (name "Net-(U$2-UART4_TXD)") (class "Default")
      (node (ref "JP3") (pin "17") (pinfunction "17_17") (pintype "passive"))
      (node (ref "U$2") (pin "59") (pinfunction "UART4_TXD_59") (pintype "passive"))
    )
    (net (code "94") (name "Net-(U$2-UART5_CTSN)") (class "Default")
      (node (ref "JP1") (pin "8") (pinfunction "8_8") (pintype "passive"))
      (node (ref "U$2") (pin "31") (pinfunction "UART5_CTSN_31") (pintype "passive"))
    )
    (net (code "95") (name "Net-(U$2-UART5_RTSN)") (class "Default")
      (node (ref "JP2") (pin "16") (pinfunction "16_16") (pintype "passive"))
      (node (ref "U$2") (pin "32") (pinfunction "UART5_RTSN_32") (pintype "passive"))
    )
    (net (code "96") (name "Net-(U$2-UART5_TXD)") (class "Default")
      (node (ref "JP1") (pin "5") (pinfunction "5_5") (pintype "passive"))
      (node (ref "U$2") (pin "37") (pinfunction "UART5_TXD_37") (pintype "passive"))
    )
    (net (code "97") (name "Net-(U$2-VDD_ADC)") (class "Default")
      (node (ref "JP4") (pin "16") (pinfunction "16_16") (pintype "passive"))
      (node (ref "U$2") (pin "78") (pinfunction "VDD_ADC_78") (pintype "passive"))
    )
    (net (code "98") (name "unconnected-(JP5-Pad1)") (class "Default")
      (node (ref "JP5") (pin "1") (pinfunction "1_1") (pintype "passive"))
    )
    (net (code "99") (name "unconnected-(JP5-Pad2)") (class "Default")
      (node (ref "JP5") (pin "2") (pinfunction "2_2") (pintype "passive"))
    )
    (net (code "100") (name "unconnected-(JP5-Pad3)") (class "Default")
      (node (ref "JP5") (pin "3") (pinfunction "3_3") (pintype "passive"))
    )
    (net (code "101") (name "unconnected-(JP5-Pad4)") (class "Default")
      (node (ref "JP5") (pin "4") (pinfunction "4_4") (pintype "passive"))
    )
    (net (code "102") (name "unconnected-(JP5-Pad5)") (class "Default")
      (node (ref "JP5") (pin "5") (pinfunction "5_5") (pintype "passive"))
    )
    (net (code "103") (name "unconnected-(JP5-Pad6)") (class "Default")
      (node (ref "JP5") (pin "6") (pinfunction "6_6") (pintype "passive"))
    )
    (net (code "104") (name "unconnected-(JP5-Pad7)") (class "Default")
      (node (ref "JP5") (pin "7") (pinfunction "7_7") (pintype "passive"))
    )
    (net (code "105") (name "unconnected-(JP5-Pad8)") (class "Default")
      (node (ref "JP5") (pin "8") (pinfunction "8_8") (pintype "passive"))
    )
    (net (code "106") (name "unconnected-(JP5-Pad9)") (class "Default")
      (node (ref "JP5") (pin "9") (pinfunction "9_9") (pintype "passive"))
    )
    (net (code "107") (name "unconnected-(JP5-Pad10)") (class "Default")
      (node (ref "JP5") (pin "10") (pinfunction "10_10") (pintype "passive"))
    )
    (net (code "108") (name "unconnected-(JP5-Pad11)") (class "Default")
      (node (ref "JP5") (pin "11") (pinfunction "11_11") (pintype "passive"))
    )
    (net (code "109") (name "unconnected-(JP6-Pad1)") (class "Default")
      (node (ref "JP6") (pin "1") (pinfunction "1_1") (pintype "passive"))
    )
    (net (code "110") (name "unconnected-(JP6-Pad2)") (class "Default")
      (node (ref "JP6") (pin "2") (pinfunction "2_2") (pintype "passive"))
    )
    (net (code "111") (name "unconnected-(JP6-Pad3)") (class "Default")
      (node (ref "JP6") (pin "3") (pinfunction "3_3") (pintype "passive"))
    )
    (net (code "112") (name "unconnected-(JP6-Pad4)") (class "Default")
      (node (ref "JP6") (pin "4") (pinfunction "4_4") (pintype "passive"))
    )
    (net (code "113") (name "unconnected-(JP6-Pad5)") (class "Default")
      (node (ref "JP6") (pin "5") (pinfunction "5_5") (pintype "passive"))
    )
    (net (code "114") (name "unconnected-(JP6-Pad6)") (class "Default")
      (node (ref "JP6") (pin "6") (pinfunction "6_6") (pintype "passive"))
    )
    (net (code "115") (name "unconnected-(JP6-Pad7)") (class "Default")
      (node (ref "JP6") (pin "7") (pinfunction "7_7") (pintype "passive"))
    )
    (net (code "116") (name "unconnected-(JP6-Pad8)") (class "Default")
      (node (ref "JP6") (pin "8") (pinfunction "8_8") (pintype "passive"))
    )
    (net (code "117") (name "unconnected-(JP6-Pad9)") (class "Default")
      (node (ref "JP6") (pin "9") (pinfunction "9_9") (pintype "passive"))
    )
    (net (code "118") (name "unconnected-(JP6-Pad10)") (class "Default")
      (node (ref "JP6") (pin "10") (pinfunction "10_10") (pintype "passive"))
    )
    (net (code "119") (name "unconnected-(JP6-Pad11)") (class "Default")
      (node (ref "JP6") (pin "11") (pinfunction "11_11") (pintype "passive"))
    )
    (net (code "120") (name "unconnected-(JP11-Pad1)") (class "Default")
      (node (ref "JP11") (pin "1") (pinfunction "1_1") (pintype "passive"))
    )
    (net (code "121") (name "unconnected-(JP11-Pad2)") (class "Default")
      (node (ref "JP11") (pin "2") (pinfunction "2_2") (pintype "passive"))
    )
    (net (code "122") (name "unconnected-(JP11-Pad3)") (class "Default")
      (node (ref "JP11") (pin "3") (pinfunction "3_3") (pintype "passive"))
    )
    (net (code "123") (name "unconnected-(JP11-Pad4)") (class "Default")
      (node (ref "JP11") (pin "4") (pinfunction "4_4") (pintype "passive"))
    )
    (net (code "124") (name "unconnected-(JP11-Pad5)") (class "Default")
      (node (ref "JP11") (pin "5") (pinfunction "5_5") (pintype "passive"))
    )
    (net (code "125") (name "unconnected-(JP11-Pad6)") (class "Default")
      (node (ref "JP11") (pin "6") (pinfunction "6_6") (pintype "passive"))
    )
    (net (code "126") (name "unconnected-(JP11-Pad7)") (class "Default")
      (node (ref "JP11") (pin "7") (pinfunction "7_7") (pintype "passive"))
    )
    (net (code "127") (name "unconnected-(JP11-Pad8)") (class "Default")
      (node (ref "JP11") (pin "8") (pinfunction "8_8") (pintype "passive"))
    )
    (net (code "128") (name "unconnected-(JP11-Pad9)") (class "Default")
      (node (ref "JP11") (pin "9") (pinfunction "9_9") (pintype "passive"))
    )
    (net (code "129") (name "unconnected-(JP11-Pad10)") (class "Default")
      (node (ref "JP11") (pin "10") (pinfunction "10_10") (pintype "passive"))
    )
    (net (code "130") (name "unconnected-(JP11-Pad11)") (class "Default")
      (node (ref "JP11") (pin "11") (pinfunction "11_11") (pintype "passive"))
    )
    (net (code "131") (name "unconnected-(JP12-Pad1)") (class "Default")
      (node (ref "JP12") (pin "1") (pinfunction "1_1") (pintype "passive"))
    )
    (net (code "132") (name "unconnected-(JP12-Pad2)") (class "Default")
      (node (ref "JP12") (pin "2") (pinfunction "2_2") (pintype "passive"))
    )
    (net (code "133") (name "unconnected-(JP12-Pad3)") (class "Default")
      (node (ref "JP12") (pin "3") (pinfunction "3_3") (pintype "passive"))
    )
    (net (code "134") (name "unconnected-(JP12-Pad4)") (class "Default")
      (node (ref "JP12") (pin "4") (pinfunction "4_4") (pintype "passive"))
    )
    (net (code "135") (name "unconnected-(JP12-Pad5)") (class "Default")
      (node (ref "JP12") (pin "5") (pinfunction "5_5") (pintype "passive"))
    )
    (net (code "136") (name "unconnected-(JP12-Pad6)") (class "Default")
      (node (ref "JP12") (pin "6") (pinfunction "6_6") (pintype "passive"))
    )
    (net (code "137") (name "unconnected-(JP12-Pad7)") (class "Default")
      (node (ref "JP12") (pin "7") (pinfunction "7_7") (pintype "passive"))
    )
    (net (code "138") (name "unconnected-(JP12-Pad8)") (class "Default")
      (node (ref "JP12") (pin "8") (pinfunction "8_8") (pintype "passive"))
    )
    (net (code "139") (name "unconnected-(JP12-Pad9)") (class "Default")
      (node (ref "JP12") (pin "9") (pinfunction "9_9") (pintype "passive"))
    )
    (net (code "140") (name "unconnected-(JP12-Pad10)") (class "Default")
      (node (ref "JP12") (pin "10") (pinfunction "10_10") (pintype "passive"))
    )
    (net (code "141") (name "unconnected-(JP12-Pad11)") (class "Default")
      (node (ref "JP12") (pin "11") (pinfunction "11_11") (pintype "passive"))
    )
    (net (code "142") (name "unconnected-(JP13-Pad1)") (class "Default")
      (node (ref "JP13") (pin "1") (pinfunction "1_1") (pintype "passive"))
    )
    (net (code "143") (name "unconnected-(JP13-Pad2)") (class "Default")
      (node (ref "JP13") (pin "2") (pinfunction "2_2") (pintype "passive"))
    )
    (net (code "144") (name "unconnected-(JP13-Pad3)") (class "Default")
      (node (ref "JP13") (pin "3") (pinfunction "3_3") (pintype "passive"))
    )
    (net (code "145") (name "unconnected-(JP13-Pad4)") (class "Default")
      (node (ref "JP13") (pin "4") (pinfunction "4_4") (pintype "passive"))
    )
    (net (code "146") (name "unconnected-(JP13-Pad5)") (class "Default")
      (node (ref "JP13") (pin "5") (pinfunction "5_5") (pintype "passive"))
    )
    (net (code "147") (name "unconnected-(JP13-Pad6)") (class "Default")
      (node (ref "JP13") (pin "6") (pinfunction "6_6") (pintype "passive"))
    )
    (net (code "148") (name "unconnected-(JP13-Pad7)") (class "Default")
      (node (ref "JP13") (pin "7") (pinfunction "7_7") (pintype "passive"))
    )
    (net (code "149") (name "unconnected-(JP13-Pad8)") (class "Default")
      (node (ref "JP13") (pin "8") (pinfunction "8_8") (pintype "passive"))
    )
    (net (code "150") (name "unconnected-(JP13-Pad9)") (class "Default")
      (node (ref "JP13") (pin "9") (pinfunction "9_9") (pintype "passive"))
    )
    (net (code "151") (name "unconnected-(JP13-Pad10)") (class "Default")
      (node (ref "JP13") (pin "10") (pinfunction "10_10") (pintype "passive"))
    )
    (net (code "152") (name "unconnected-(JP13-Pad11)") (class "Default")
      (node (ref "JP13") (pin "11") (pinfunction "11_11") (pintype "passive"))
    )
    (net (code "153") (name "unconnected-(JP14-Pad1)") (class "Default")
      (node (ref "JP14") (pin "1") (pinfunction "1_1") (pintype "passive"))
    )
    (net (code "154") (name "unconnected-(JP14-Pad2)") (class "Default")
      (node (ref "JP14") (pin "2") (pinfunction "2_2") (pintype "passive"))
    )
    (net (code "155") (name "unconnected-(JP14-Pad3)") (class "Default")
      (node (ref "JP14") (pin "3") (pinfunction "3_3") (pintype "passive"))
    )
    (net (code "156") (name "unconnected-(JP14-Pad4)") (class "Default")
      (node (ref "JP14") (pin "4") (pinfunction "4_4") (pintype "passive"))
    )
    (net (code "157") (name "unconnected-(JP14-Pad5)") (class "Default")
      (node (ref "JP14") (pin "5") (pinfunction "5_5") (pintype "passive"))
    )
    (net (code "158") (name "unconnected-(JP14-Pad6)") (class "Default")
      (node (ref "JP14") (pin "6") (pinfunction "6_6") (pintype "passive"))
    )
    (net (code "159") (name "unconnected-(JP14-Pad7)") (class "Default")
      (node (ref "JP14") (pin "7") (pinfunction "7_7") (pintype "passive"))
    )
    (net (code "160") (name "unconnected-(JP14-Pad8)") (class "Default")
      (node (ref "JP14") (pin "8") (pinfunction "8_8") (pintype "passive"))
    )
    (net (code "161") (name "unconnected-(JP14-Pad9)") (class "Default")
      (node (ref "JP14") (pin "9") (pinfunction "9_9") (pintype "passive"))
    )
    (net (code "162") (name "unconnected-(JP14-Pad10)") (class "Default")
      (node (ref "JP14") (pin "10") (pinfunction "10_10") (pintype "passive"))
    )
    (net (code "163") (name "unconnected-(JP14-Pad11)") (class "Default")
      (node (ref "JP14") (pin "11") (pinfunction "11_11") (pintype "passive"))
    )
    (net (code "164") (name "unconnected-(JP15-Pad1)") (class "Default")
      (node (ref "JP15") (pin "1") (pinfunction "1_1") (pintype "passive"))
    )
    (net (code "165") (name "unconnected-(JP15-Pad2)") (class "Default")
      (node (ref "JP15") (pin "2") (pinfunction "2_2") (pintype "passive"))
    )
    (net (code "166") (name "unconnected-(JP15-Pad3)") (class "Default")
      (node (ref "JP15") (pin "3") (pinfunction "3_3") (pintype "passive"))
    )
    (net (code "167") (name "unconnected-(JP15-Pad4)") (class "Default")
      (node (ref "JP15") (pin "4") (pinfunction "4_4") (pintype "passive"))
    )
    (net (code "168") (name "unconnected-(JP15-Pad5)") (class "Default")
      (node (ref "JP15") (pin "5") (pinfunction "5_5") (pintype "passive"))
    )
    (net (code "169") (name "unconnected-(JP15-Pad6)") (class "Default")
      (node (ref "JP15") (pin "6") (pinfunction "6_6") (pintype "passive"))
    )
    (net (code "170") (name "unconnected-(JP15-Pad7)") (class "Default")
      (node (ref "JP15") (pin "7") (pinfunction "7_7") (pintype "passive"))
    )
    (net (code "171") (name "unconnected-(JP15-Pad8)") (class "Default")
      (node (ref "JP15") (pin "8") (pinfunction "8_8") (pintype "passive"))
    )
    (net (code "172") (name "unconnected-(JP15-Pad9)") (class "Default")
      (node (ref "JP15") (pin "9") (pinfunction "9_9") (pintype "passive"))
    )
    (net (code "173") (name "unconnected-(JP15-Pad10)") (class "Default")
      (node (ref "JP15") (pin "10") (pinfunction "10_10") (pintype "passive"))
    )
    (net (code "174") (name "unconnected-(JP15-Pad11)") (class "Default")
      (node (ref "JP15") (pin "11") (pinfunction "11_11") (pintype "passive"))
    )
    (net (code "175") (name "unconnected-(JP16-Pad1)") (class "Default")
      (node (ref "JP16") (pin "1") (pinfunction "1_1") (pintype "passive"))
    )
    (net (code "176") (name "unconnected-(JP16-Pad2)") (class "Default")
      (node (ref "JP16") (pin "2") (pinfunction "2_2") (pintype "passive"))
    )
    (net (code "177") (name "unconnected-(JP16-Pad3)") (class "Default")
      (node (ref "JP16") (pin "3") (pinfunction "3_3") (pintype "passive"))
    )
    (net (code "178") (name "unconnected-(JP16-Pad4)") (class "Default")
      (node (ref "JP16") (pin "4") (pinfunction "4_4") (pintype "passive"))
    )
    (net (code "179") (name "unconnected-(JP16-Pad5)") (class "Default")
      (node (ref "JP16") (pin "5") (pinfunction "5_5") (pintype "passive"))
    )
    (net (code "180") (name "unconnected-(JP16-Pad6)") (class "Default")
      (node (ref "JP16") (pin "6") (pinfunction "6_6") (pintype "passive"))
    )
    (net (code "181") (name "unconnected-(JP16-Pad7)") (class "Default")
      (node (ref "JP16") (pin "7") (pinfunction "7_7") (pintype "passive"))
    )
    (net (code "182") (name "unconnected-(JP16-Pad8)") (class "Default")
      (node (ref "JP16") (pin "8") (pinfunction "8_8") (pintype "passive"))
    )
    (net (code "183") (name "unconnected-(JP16-Pad9)") (class "Default")
      (node (ref "JP16") (pin "9") (pinfunction "9_9") (pintype "passive"))
    )
    (net (code "184") (name "unconnected-(JP16-Pad10)") (class "Default")
      (node (ref "JP16") (pin "10") (pinfunction "10_10") (pintype "passive"))
    )
    (net (code "185") (name "unconnected-(JP16-Pad11)") (class "Default")
      (node (ref "JP16") (pin "11") (pinfunction "11_11") (pintype "passive"))
    )
    (net (code "186") (name "unconnected-(JP17-Pad1)") (class "Default")
      (node (ref "JP17") (pin "1") (pinfunction "1_1") (pintype "passive"))
    )
    (net (code "187") (name "unconnected-(JP17-Pad2)") (class "Default")
      (node (ref "JP17") (pin "2") (pinfunction "2_2") (pintype "passive"))
    )
    (net (code "188") (name "unconnected-(JP17-Pad3)") (class "Default")
      (node (ref "JP17") (pin "3") (pinfunction "3_3") (pintype "passive"))
    )
    (net (code "189") (name "unconnected-(JP17-Pad4)") (class "Default")
      (node (ref "JP17") (pin "4") (pinfunction "4_4") (pintype "passive"))
    )
    (net (code "190") (name "unconnected-(JP17-Pad5)") (class "Default")
      (node (ref "JP17") (pin "5") (pinfunction "5_5") (pintype "passive"))
    )
    (net (code "191") (name "unconnected-(JP17-Pad6)") (class "Default")
      (node (ref "JP17") (pin "6") (pinfunction "6_6") (pintype "passive"))
    )
    (net (code "192") (name "unconnected-(JP17-Pad7)") (class "Default")
      (node (ref "JP17") (pin "7") (pinfunction "7_7") (pintype "passive"))
    )
    (net (code "193") (name "unconnected-(JP17-Pad8)") (class "Default")
      (node (ref "JP17") (pin "8") (pinfunction "8_8") (pintype "passive"))
    )
    (net (code "194") (name "unconnected-(JP17-Pad9)") (class "Default")
      (node (ref "JP17") (pin "9") (pinfunction "9_9") (pintype "passive"))
    )
    (net (code "195") (name "unconnected-(JP17-Pad10)") (class "Default")
      (node (ref "JP17") (pin "10") (pinfunction "10_10") (pintype "passive"))
    )
    (net (code "196") (name "unconnected-(JP17-Pad11)") (class "Default")
      (node (ref "JP17") (pin "11") (pinfunction "11_11") (pintype "passive"))
    )
    (net (code "197") (name "unconnected-(JP18-Pad1)") (class "Default")
      (node (ref "JP18") (pin "1") (pinfunction "1_1") (pintype "passive"))
    )
    (net (code "198") (name "unconnected-(JP18-Pad2)") (class "Default")
      (node (ref "JP18") (pin "2") (pinfunction "2_2") (pintype "passive"))
    )
    (net (code "199") (name "unconnected-(JP18-Pad3)") (class "Default")
      (node (ref "JP18") (pin "3") (pinfunction "3_3") (pintype "passive"))
    )
    (net (code "200") (name "unconnected-(JP18-Pad4)") (class "Default")
      (node (ref "JP18") (pin "4") (pinfunction "4_4") (pintype "passive"))
    )
    (net (code "201") (name "unconnected-(JP18-Pad5)") (class "Default")
      (node (ref "JP18") (pin "5") (pinfunction "5_5") (pintype "passive"))
    )
    (net (code "202") (name "unconnected-(JP18-Pad6)") (class "Default")
      (node (ref "JP18") (pin "6") (pinfunction "6_6") (pintype "passive"))
    )
    (net (code "203") (name "unconnected-(JP18-Pad7)") (class "Default")
      (node (ref "JP18") (pin "7") (pinfunction "7_7") (pintype "passive"))
    )
    (net (code "204") (name "unconnected-(JP18-Pad8)") (class "Default")
      (node (ref "JP18") (pin "8") (pinfunction "8_8") (pintype "passive"))
    )
    (net (code "205") (name "unconnected-(JP18-Pad9)") (class "Default")
      (node (ref "JP18") (pin "9") (pinfunction "9_9") (pintype "passive"))
    )
    (net (code "206") (name "unconnected-(JP18-Pad10)") (class "Default")
      (node (ref "JP18") (pin "10") (pinfunction "10_10") (pintype "passive"))
    )
    (net (code "207") (name "unconnected-(JP18-Pad11)") (class "Default")
      (node (ref "JP18") (pin "11") (pinfunction "11_11") (pintype "passive"))
    )
    (net (code "208") (name "unconnected-(JP19-Pad1)") (class "Default")
      (node (ref "JP19") (pin "1") (pinfunction "1_1") (pintype "passive"))
    )
    (net (code "209") (name "unconnected-(JP19-Pad2)") (class "Default")
      (node (ref "JP19") (pin "2") (pinfunction "2_2") (pintype "passive"))
    )
    (net (code "210") (name "unconnected-(JP19-Pad3)") (class "Default")
      (node (ref "JP19") (pin "3") (pinfunction "3_3") (pintype "passive"))
    )
    (net (code "211") (name "unconnected-(JP19-Pad4)") (class "Default")
      (node (ref "JP19") (pin "4") (pinfunction "4_4") (pintype "passive"))
    )
    (net (code "212") (name "unconnected-(JP19-Pad5)") (class "Default")
      (node (ref "JP19") (pin "5") (pinfunction "5_5") (pintype "passive"))
    )
    (net (code "213") (name "unconnected-(JP19-Pad6)") (class "Default")
      (node (ref "JP19") (pin "6") (pinfunction "6_6") (pintype "passive"))
    )
    (net (code "214") (name "unconnected-(JP19-Pad7)") (class "Default")
      (node (ref "JP19") (pin "7") (pinfunction "7_7") (pintype "passive"))
    )
    (net (code "215") (name "unconnected-(JP19-Pad8)") (class "Default")
      (node (ref "JP19") (pin "8") (pinfunction "8_8") (pintype "passive"))
    )
    (net (code "216") (name "unconnected-(JP19-Pad9)") (class "Default")
      (node (ref "JP19") (pin "9") (pinfunction "9_9") (pintype "passive"))
    )
    (net (code "217") (name "unconnected-(JP19-Pad10)") (class "Default")
      (node (ref "JP19") (pin "10") (pinfunction "10_10") (pintype "passive"))
    )
    (net (code "218") (name "unconnected-(JP19-Pad11)") (class "Default")
      (node (ref "JP19") (pin "11") (pinfunction "11_11") (pintype "passive"))
    )
    (net (code "219") (name "unconnected-(JP20-Pad1)") (class "Default")
      (node (ref "JP20") (pin "1") (pinfunction "1_1") (pintype "passive"))
    )
    (net (code "220") (name "unconnected-(JP20-Pad2)") (class "Default")
      (node (ref "JP20") (pin "2") (pinfunction "2_2") (pintype "passive"))
    )
    (net (code "221") (name "unconnected-(JP20-Pad3)") (class "Default")
      (node (ref "JP20") (pin "3") (pinfunction "3_3") (pintype "passive"))
    )
    (net (code "222") (name "unconnected-(JP20-Pad4)") (class "Default")
      (node (ref "JP20") (pin "4") (pinfunction "4_4") (pintype "passive"))
    )
    (net (code "223") (name "unconnected-(JP20-Pad5)") (class "Default")
      (node (ref "JP20") (pin "5") (pinfunction "5_5") (pintype "passive"))
    )
    (net (code "224") (name "unconnected-(JP20-Pad6)") (class "Default")
      (node (ref "JP20") (pin "6") (pinfunction "6_6") (pintype "passive"))
    )
    (net (code "225") (name "unconnected-(JP20-Pad7)") (class "Default")
      (node (ref "JP20") (pin "7") (pinfunction "7_7") (pintype "passive"))
    )
    (net (code "226") (name "unconnected-(JP20-Pad8)") (class "Default")
      (node (ref "JP20") (pin "8") (pinfunction "8_8") (pintype "passive"))
    )
    (net (code "227") (name "unconnected-(JP20-Pad9)") (class "Default")
      (node (ref "JP20") (pin "9") (pinfunction "9_9") (pintype "passive"))
    )
    (net (code "228") (name "unconnected-(JP20-Pad10)") (class "Default")
      (node (ref "JP20") (pin "10") (pinfunction "10_10") (pintype "passive"))
    )
    (net (code "229") (name "unconnected-(JP20-Pad11)") (class "Default")
      (node (ref "JP20") (pin "11") (pinfunction "11_11") (pintype "passive"))
    )
    (net (code "230") (name "unconnected-(JP21-Pad1)") (class "Default")
      (node (ref "JP21") (pin "1") (pinfunction "1_1") (pintype "passive"))
    )
    (net (code "231") (name "unconnected-(JP21-Pad2)") (class "Default")
      (node (ref "JP21") (pin "2") (pinfunction "2_2") (pintype "passive"))
    )
    (net (code "232") (name "unconnected-(JP21-Pad3)") (class "Default")
      (node (ref "JP21") (pin "3") (pinfunction "3_3") (pintype "passive"))
    )
    (net (code "233") (name "unconnected-(JP21-Pad4)") (class "Default")
      (node (ref "JP21") (pin "4") (pinfunction "4_4") (pintype "passive"))
    )
    (net (code "234") (name "unconnected-(JP21-Pad5)") (class "Default")
      (node (ref "JP21") (pin "5") (pinfunction "5_5") (pintype "passive"))
    )
    (net (code "235") (name "unconnected-(JP21-Pad6)") (class "Default")
      (node (ref "JP21") (pin "6") (pinfunction "6_6") (pintype "passive"))
    )
    (net (code "236") (name "unconnected-(JP21-Pad7)") (class "Default")
      (node (ref "JP21") (pin "7") (pinfunction "7_7") (pintype "passive"))
    )
    (net (code "237") (name "unconnected-(JP21-Pad8)") (class "Default")
      (node (ref "JP21") (pin "8") (pinfunction "8_8") (pintype "passive"))
    )
    (net (code "238") (name "unconnected-(JP21-Pad9)") (class "Default")
      (node (ref "JP21") (pin "9") (pinfunction "9_9") (pintype "passive"))
    )
    (net (code "239") (name "unconnected-(JP21-Pad10)") (class "Default")
      (node (ref "JP21") (pin "10") (pinfunction "10_10") (pintype "passive"))
    )
    (net (code "240") (name "unconnected-(JP21-Pad11)") (class "Default")
      (node (ref "JP21") (pin "11") (pinfunction "11_11") (pintype "passive"))
    )
    (net (code "241") (name "unconnected-(JP22-Pad1)") (class "Default")
      (node (ref "JP22") (pin "1") (pinfunction "1_1") (pintype "passive"))
    )
    (net (code "242") (name "unconnected-(JP22-Pad2)") (class "Default")
      (node (ref "JP22") (pin "2") (pinfunction "2_2") (pintype "passive"))
    )
    (net (code "243") (name "unconnected-(JP22-Pad3)") (class "Default")
      (node (ref "JP22") (pin "3") (pinfunction "3_3") (pintype "passive"))
    )
    (net (code "244") (name "unconnected-(JP22-Pad4)") (class "Default")
      (node (ref "JP22") (pin "4") (pinfunction "4_4") (pintype "passive"))
    )
    (net (code "245") (name "unconnected-(JP22-Pad5)") (class "Default")
      (node (ref "JP22") (pin "5") (pinfunction "5_5") (pintype "passive"))
    )
    (net (code "246") (name "unconnected-(JP22-Pad6)") (class "Default")
      (node (ref "JP22") (pin "6") (pinfunction "6_6") (pintype "passive"))
    )
    (net (code "247") (name "unconnected-(JP22-Pad7)") (class "Default")
      (node (ref "JP22") (pin "7") (pinfunction "7_7") (pintype "passive"))
    )
    (net (code "248") (name "unconnected-(JP22-Pad8)") (class "Default")
      (node (ref "JP22") (pin "8") (pinfunction "8_8") (pintype "passive"))
    )
    (net (code "249") (name "unconnected-(JP22-Pad9)") (class "Default")
      (node (ref "JP22") (pin "9") (pinfunction "9_9") (pintype "passive"))
    )
    (net (code "250") (name "unconnected-(JP22-Pad10)") (class "Default")
      (node (ref "JP22") (pin "10") (pinfunction "10_10") (pintype "passive"))
    )
    (net (code "251") (name "unconnected-(JP22-Pad11)") (class "Default")
      (node (ref "JP22") (pin "11") (pinfunction "11_11") (pintype "passive"))
    )
    (net (code "252") (name "unconnected-(JP23-Pad1)") (class "Default")
      (node (ref "JP23") (pin "1") (pinfunction "1_1") (pintype "passive"))
    )
    (net (code "253") (name "unconnected-(JP23-Pad2)") (class "Default")
      (node (ref "JP23") (pin "2") (pinfunction "2_2") (pintype "passive"))
    )
    (net (code "254") (name "unconnected-(JP23-Pad3)") (class "Default")
      (node (ref "JP23") (pin "3") (pinfunction "3_3") (pintype "passive"))
    )
    (net (code "255") (name "unconnected-(JP23-Pad4)") (class "Default")
      (node (ref "JP23") (pin "4") (pinfunction "4_4") (pintype "passive"))
    )
    (net (code "256") (name "unconnected-(JP23-Pad5)") (class "Default")
      (node (ref "JP23") (pin "5") (pinfunction "5_5") (pintype "passive"))
    )
    (net (code "257") (name "unconnected-(JP23-Pad6)") (class "Default")
      (node (ref "JP23") (pin "6") (pinfunction "6_6") (pintype "passive"))
    )
    (net (code "258") (name "unconnected-(JP23-Pad7)") (class "Default")
      (node (ref "JP23") (pin "7") (pinfunction "7_7") (pintype "passive"))
    )
    (net (code "259") (name "unconnected-(JP23-Pad8)") (class "Default")
      (node (ref "JP23") (pin "8") (pinfunction "8_8") (pintype "passive"))
    )
    (net (code "260") (name "unconnected-(JP23-Pad9)") (class "Default")
      (node (ref "JP23") (pin "9") (pinfunction "9_9") (pintype "passive"))
    )
    (net (code "261") (name "unconnected-(JP23-Pad10)") (class "Default")
      (node (ref "JP23") (pin "10") (pinfunction "10_10") (pintype "passive"))
    )
    (net (code "262") (name "unconnected-(JP23-Pad11)") (class "Default")
      (node (ref "JP23") (pin "11") (pinfunction "11_11") (pintype "passive"))
    )
    (net (code "263") (name "unconnected-(JP26-Pad1)") (class "Default")
      (node (ref "JP26") (pin "1") (pinfunction "1_1") (pintype "passive"))
    )
    (net (code "264") (name "unconnected-(JP26-Pad2)") (class "Default")
      (node (ref "JP26") (pin "2") (pinfunction "2_2") (pintype "passive"))
    )
    (net (code "265") (name "unconnected-(JP26-Pad3)") (class "Default")
      (node (ref "JP26") (pin "3") (pinfunction "3_3") (pintype "passive"))
    )
    (net (code "266") (name "unconnected-(JP26-Pad4)") (class "Default")
      (node (ref "JP26") (pin "4") (pinfunction "4_4") (pintype "passive"))
    )
    (net (code "267") (name "unconnected-(JP26-Pad5)") (class "Default")
      (node (ref "JP26") (pin "5") (pinfunction "5_5") (pintype "passive"))
    )
    (net (code "268") (name "unconnected-(JP26-Pad6)") (class "Default")
      (node (ref "JP26") (pin "6") (pinfunction "6_6") (pintype "passive"))
    )
  )
)
